# Compass.net
KiCad netlist of a schematic drawn in Altium Designer
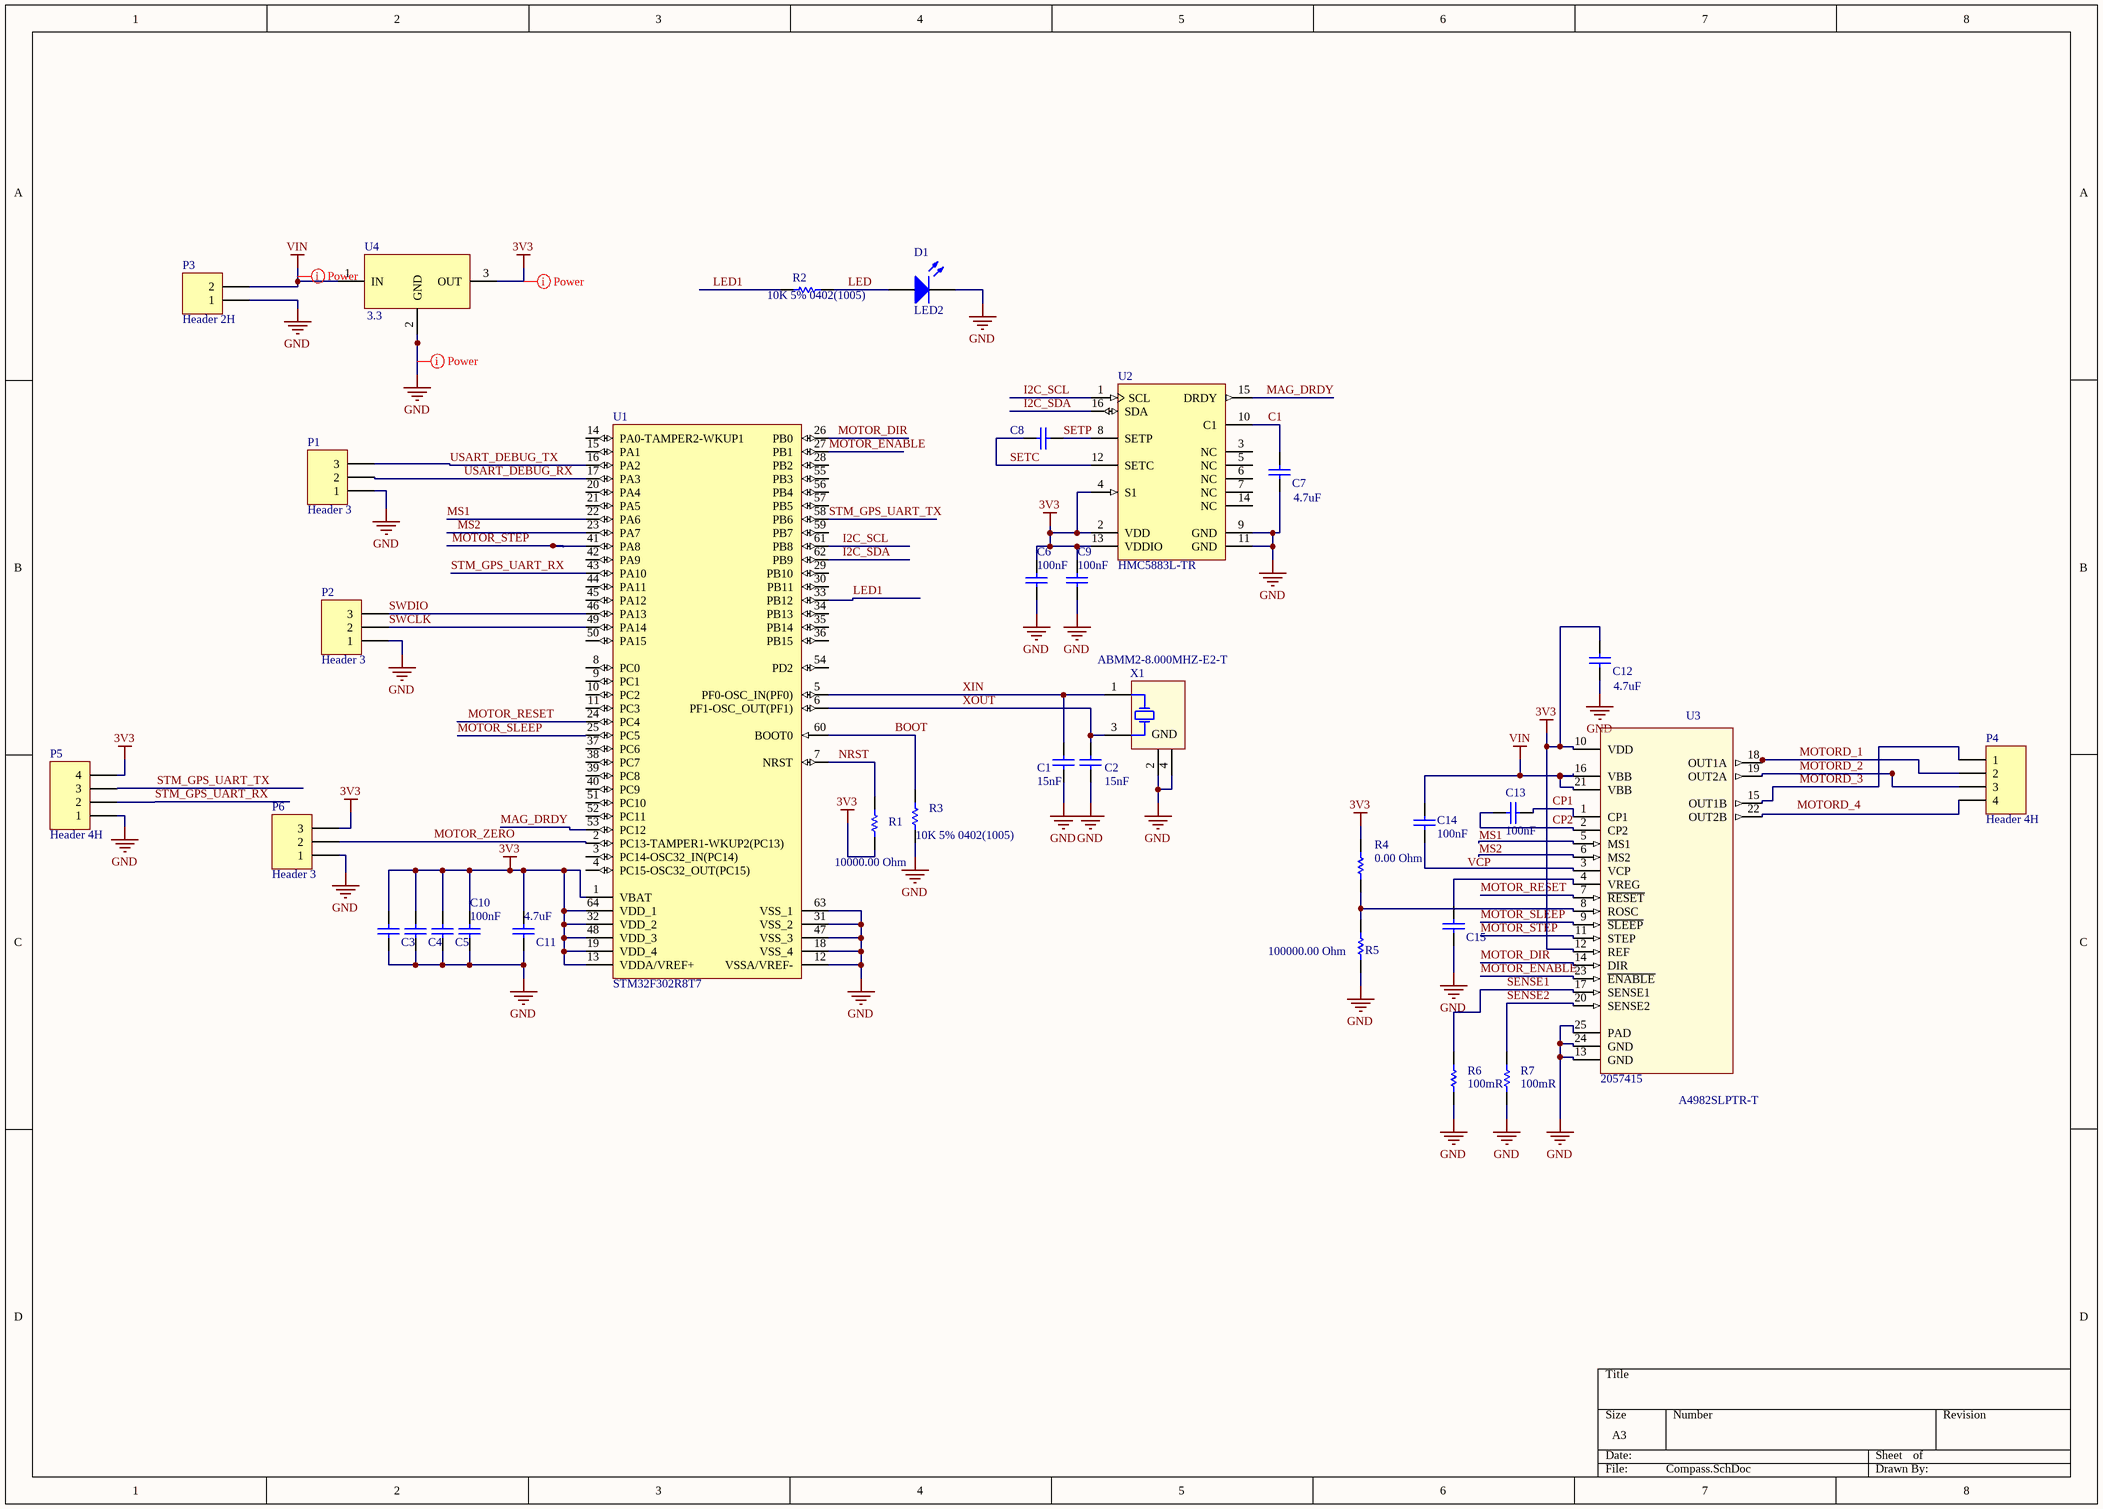
[diagram p0: Compass.SchDoc]

(export (version "E")
  (design (tool "Eeschema 10.0.6"))
  (components
    (comp (ref "C1")
      (value "15nF")
      (footprint "CAPC0402(1005)60_M")
      (description "CAP 15nF 6.3V ±20% 0402 (1005 Metric) Thickness 0.6mm SMD")
      (fields (field (name "TOLERANCE") "Â±20%") (field (name "Comment") "CAP 15nF 6.3V 0402(1005)"))
      (libsource (lib "Altium Content Vault") (part "CMP-1034-01907-1"))
    )
    (comp (ref "C2")
      (value "15nF")
      (footprint "CAPC0402(1005)60_M")
      (description "CAP 15nF 6.3V ±20% 0402 (1005 Metric) Thickness 0.6mm SMD")
      (fields (field (name "TOLERANCE") "Â±20%") (field (name "Comment") "CAP 15nF 6.3V 0402(1005)"))
      (libsource (lib "Altium Content Vault") (part "CMP-1034-01907-1"))
    )
    (comp (ref "C3")
      (value "CAP 100nF 6.3V 0603(1608)")
      (footprint "CAPC0603(1608)100_M")
      (description "CAP 100nF 6.3V ±10% 0603 (1608 Metric) Thickness 1mm SMD")
      (fields (field (name "TOLERANCE") "Â±10%"))
      (libsource (lib "Altium Content Vault") (part "CAP"))
    )
    (comp (ref "C4")
      (value "CAP 100nF 6.3V 0603(1608)")
      (footprint "CAPC0603(1608)100_M")
      (description "CAP 100nF 6.3V ±10% 0603 (1608 Metric) Thickness 1mm SMD")
      (fields (field (name "TOLERANCE") "Â±10%"))
      (libsource (lib "Altium Content Vault") (part "CAP"))
    )
    (comp (ref "C5")
      (value "CAP 100nF 6.3V 0603(1608)")
      (footprint "CAPC0603(1608)100_M")
      (description "CAP 100nF 6.3V ±10% 0603 (1608 Metric) Thickness 1mm SMD")
      (fields (field (name "TOLERANCE") "Â±10%"))
      (libsource (lib "Altium Content Vault") (part "CAP"))
    )
    (comp (ref "C6")
      (value "100nF")
      (footprint "CAPC0603(1608)100_M")
      (description "CAP 100nF 6.3V ±10% 0603 (1608 Metric) Thickness 1mm SMD")
      (fields (field (name "TOLERANCE") "Â±10%") (field (name "Comment") "CAP 100nF 6.3V 0603(1608)"))
      (libsource (lib "Altium Content Vault") (part "CMP-1035-02576-1"))
    )
    (comp (ref "C7")
      (value "4.7uF")
      (footprint "CAPC0603(1608)100_M")
      (description "CAP 4.7uF 6.3V ±20% 0603 (1608 Metric) Thickness 1mm SMD")
      (fields (field (name "TOLERANCE") "Â±20%") (field (name "Comment") "CAP 4.7uF 6.3V 0603(1608)"))
      (libsource (lib "Altium Content Vault") (part "CMP-1035-02782-1"))
    )
    (comp (ref "C8")
      (value "CAP 220nF 6.3V 0402(1005)")
      (footprint "CAPC0402(1005)60_L")
      (description "CAP 220nF 6.3V ±10% 0402 (1005 Metric) Thickness 0.6mm SMD")
      (fields (field (name "TOLERANCE") "Â±10%"))
      (libsource (lib "Altium Content Vault") (part "CAP"))
    )
    (comp (ref "C9")
      (value "100nF")
      (footprint "CAPC0603(1608)100_M")
      (description "CAP 100nF 6.3V ±10% 0603 (1608 Metric) Thickness 1mm SMD")
      (fields (field (name "TOLERANCE") "Â±10%") (field (name "Comment") "CAP 100nF 6.3V 0603(1608)"))
      (libsource (lib "Altium Content Vault") (part "CMP-1035-02576-1"))
    )
    (comp (ref "C10")
      (value "100nF")
      (footprint "CAPC0603(1608)100_M")
      (description "CAP 100nF 6.3V ±10% 0603 (1608 Metric) Thickness 1mm SMD")
      (fields (field (name "TOLERANCE") "Â±10%") (field (name "Comment") "CAP 100nF 6.3V 0603(1608)"))
      (libsource (lib "Altium Content Vault") (part "CMP-1035-02576-1"))
    )
    (comp (ref "C11")
      (value "4.7uF")
      (footprint "CAPC0603(1608)100_M")
      (description "CAP 4.7uF 6.3V ±20% 0603 (1608 Metric) Thickness 1mm SMD")
      (fields (field (name "TOLERANCE") "Â±20%") (field (name "Comment") "CAP 4.7uF 6.3V 0603(1608)"))
      (libsource (lib "Altium Content Vault") (part "CMP-1035-02782-1"))
    )
    (comp (ref "C12")
      (value "4.7uF")
      (footprint "CAPC0603(1608)100_M")
      (description "CAP 4.7uF 6.3V ±20% 0603 (1608 Metric) Thickness 1mm SMD")
      (fields (field (name "TOLERANCE") "Â±20%") (field (name "Comment") "CAP 4.7uF 6.3V 0603(1608)"))
      (libsource (lib "Altium Content Vault") (part "CMP-1035-02782-1"))
    )
    (comp (ref "C13")
      (value "100nF")
      (footprint "CAPC0603(1608)100_M")
      (description "CAP 100nF 6.3V ±10% 0603 (1608 Metric) Thickness 1mm SMD")
      (fields (field (name "TOLERANCE") "Â±10%") (field (name "Comment") "CAP 100nF 6.3V 0603(1608)"))
      (libsource (lib "Altium Content Vault") (part "CMP-1035-02576-1"))
    )
    (comp (ref "C14")
      (value "100nF")
      (footprint "CAPC0603(1608)100_M")
      (description "CAP 100nF 6.3V ±10% 0603 (1608 Metric) Thickness 1mm SMD")
      (fields (field (name "TOLERANCE") "Â±10%") (field (name "Comment") "CAP 100nF 6.3V 0603(1608)"))
      (libsource (lib "Altium Content Vault") (part "CMP-1035-02576-1"))
    )
    (comp (ref "C15")
      (value "CAP 220nF 6.3V 0402(1005)")
      (footprint "CAPC0402(1005)60_L")
      (description "CAP 220nF 6.3V ±10% 0402 (1005 Metric) Thickness 0.6mm SMD")
      (fields (field (name "TOLERANCE") "Â±10%"))
      (libsource (lib "Altium Content Vault") (part "CAP"))
    )
    (comp (ref "D1")
      (value "LED2")
      (footprint "3.2X1.6X1.1")
      (description "Typical RED, GREEN, YELLOW, AMBER GaAs LED")
      (fields (field (name "PUBLISHER") "Altium Limited"))
      (libsource (lib "Miscellaneous Devices") (part "LED2"))
    )
    (comp (ref "P1")
      (value "Header 3")
      (footprint "HDR1X3")
      (description "Header, 3-Pin")
      (fields (field (name "PUBLISHER") "Altium Limited"))
      (libsource (lib "Miscellaneous Connectors") (part "Header 3"))
    )
    (comp (ref "P2")
      (value "Header 3")
      (footprint "HDR1X3")
      (description "Header, 3-Pin")
      (fields (field (name "PUBLISHER") "Altium Limited"))
      (libsource (lib "Miscellaneous Connectors") (part "Header 3"))
    )
    (comp (ref "P3")
      (value "Header 2H")
      (footprint "HDR1X2H")
      (description "Header, 2-Pin, Right Angle")
      (fields (field (name "PUBLISHER") "Altium Limited"))
      (libsource (lib "Miscellaneous Connectors") (part "Header 2H"))
    )
    (comp (ref "P4")
      (value "Header 4H")
      (footprint "HDR1X4H")
      (description "Header, 4-Pin, Right Angle")
      (fields (field (name "PUBLISHER") "Altium Limited"))
      (libsource (lib "Miscellaneous Connectors") (part "Header 4H"))
    )
    (comp (ref "P5")
      (value "Header 4H")
      (footprint "HDR1X4H")
      (description "Header, 4-Pin, Right Angle")
      (fields (field (name "PUBLISHER") "Altium Limited"))
      (libsource (lib "") (part "Header 4H_1"))
    )
    (comp (ref "P6")
      (value "Header 3")
      (footprint "HDR1X3")
      (description "Header, 3-Pin")
      (fields (field (name "PUBLISHER") "Altium Limited"))
      (libsource (lib "Miscellaneous Connectors") (part "Header 3"))
    )
    (comp (ref "R1")
      (value "10000.00 Ohm")
      (footprint "RESC0402(1005)_N")
      (description "10K 0.063W 5% 0402 (1005 Metric)  SMD")
      (fields (field (name "TOLERANCE") "5 %") (field (name "POWER") "0.063 W"))
      (libsource (lib "Altium Content Vault") (part "CMP-1011-00098-1"))
    )
    (comp (ref "R2")
      (value "10K 5% 0402(1005)")
      (footprint "RESC0402(1005)_N")
      (description "10K 0.063W 5% 0402 (1005 Metric)  SMD")
      (fields (field (name "TOLERANCE") "5 %") (field (name "POWER") "0.063 W"))
      (libsource (lib "Altium Content Vault") (part "CMP-1011-00098-1"))
    )
    (comp (ref "R3")
      (value "10K 5% 0402(1005)")
      (footprint "RESC0402(1005)_N")
      (description "10K 0.063W 5% 0402 (1005 Metric)  SMD")
      (fields (field (name "TOLERANCE") "5 %") (field (name "POWER") "0.063 W"))
      (libsource (lib "Altium Content Vault") (part "CMP-1011-00098-1"))
    )
    (comp (ref "R4")
      (value "0.00 Ohm")
      (footprint "RESC0402(1005)_N")
      (description "Jumper 0402 (1005 Metric)")
      (fields (field (name "TOLERANCE") "None") (field (name "Comment") "Jumper 0402(1005)"))
      (libsource (lib "Altium Content Vault") (part "CMP-1011-00001-1"))
    )
    (comp (ref "R5")
      (value "100000.00 Ohm")
      (footprint "RESC0402(1005)_M")
      (description "100K 0.063W 1% 0402 (1005 Metric)  SMD")
      (fields (field (name "POWER") "0.063 W") (field (name "TOLERANCE") "1 %"))
      (libsource (lib "Altium Content Vault") (part "CMP-1011-00736-1"))
    )
    (comp (ref "R6")
      (value "100mR")
      (footprint "RESC0603(1608)_L")
      (description "0603 (1608 Metric) Chip Resistor")
      (fields (field (name "Comment") "RES0603"))
      (libsource (lib "Altium Content Vault") (part "CMP-1591-00001-1"))
    )
    (comp (ref "R7")
      (value "100mR")
      (footprint "RESC0603(1608)_L")
      (description "0603 (1608 Metric) Chip Resistor")
      (fields (field (name "Comment") "RES0603"))
      (libsource (lib "Altium Content Vault") (part "CMP-1591-00001-1"))
    )
    (comp (ref "U1")
      (value "STM32F302R8T7")
      (footprint "STM-LQFP64_N")
      (libsource (lib "Altium Content Vault") (part "MC-ARM-STM32F30X-LQFP64"))
    )
    (comp (ref "U2")
      (value "HMC5883L-TR")
      (footprint "HONEY-LPCC-16_V")
      (description "Three-Axis Digital Compass IC, 2.16 to 3.6 V, -30 to 85 degC, 16-Pin PLCC, RoHS, Tape and Reel")
      (fields (field (name "MANUFACTURER") "Honeywell"))
      (libsource (lib "Altium Content Vault") (part "HONEY-HMC5883L-TR-LPCC-16"))
    )
    (comp (ref "U3")
      (value "A4982SLPTR-T")
      (footprint "*SOP65P640X120-25N")
      (description "DMOS Microstepping Driver with Translator and Overcurrent Protection")
      (fields (field (name "MF") "Allegro") (field (name "SUPPLIER PART NUMBER 1") "2057415"))
      (libsource (lib "A4982SLPTR-T") (part "A4982SLPTR-T"))
    )
    (comp (ref "U4")
      (value "3.3")
      (footprint "TR05:SIP-3")
      (description "3V3 SMPS")
      (libsource (lib "TR05") (part "PSU"))
    )
    (comp (ref "X1")
      (value "ABMM2-8.000MHZ-E2-T")
      (footprint "ABRA-ABMM2-4_V")
      (fields (field (name "MANUFACTURER") "Abracon"))
      (libsource (lib "Altium Content Vault") (part "ABRA-XTAL_1-3-4"))
    )
  )
  (nets
    (net (code "1") (name "/BOOT") (class "Default")
      (node (ref "R3") (pin "2") (pinfunction "2_2") (pintype "passive"))
      (node (ref "U1") (pin "60") (pinfunction "BOOT0_60") (pintype "input"))
    )
    (net (code "2") (name "/C1") (class "Default")
      (node (ref "C7") (pin "2") (pinfunction "2_2") (pintype "passive"))
      (node (ref "U2") (pin "10") (pinfunction "C1_10") (pintype "passive"))
    )
    (net (code "3") (name "/CP1") (class "Default")
      (node (ref "C13") (pin "1") (pinfunction "1_1") (pintype "passive"))
      (node (ref "U3") (pin "1") (pinfunction "CP1_1") (pintype "passive"))
    )
    (net (code "4") (name "/CP2") (class "Default")
      (node (ref "C13") (pin "2") (pinfunction "2_2") (pintype "passive"))
      (node (ref "U3") (pin "2") (pinfunction "CP2_2") (pintype "passive"))
    )
    (net (code "5") (name "/I2C_SCL") (class "Default")
      (node (ref "U1") (pin "61") (pinfunction "PB8_61") (pintype "bidirectional"))
      (node (ref "U2") (pin "1") (pinfunction "SCL_1") (pintype "input"))
    )
    (net (code "6") (name "/I2C_SDA") (class "Default")
      (node (ref "U1") (pin "62") (pinfunction "PB9_62") (pintype "bidirectional"))
      (node (ref "U2") (pin "16") (pinfunction "SDA_16") (pintype "bidirectional"))
    )
    (net (code "7") (name "/LED") (class "Default")
      (node (ref "D1") (pin "1") (pinfunction "A_1") (pintype "passive"))
      (node (ref "R2") (pin "1") (pinfunction "1_1") (pintype "passive"))
    )
    (net (code "8") (name "/LED1") (class "Default")
      (node (ref "R2") (pin "2") (pinfunction "2_2") (pintype "passive"))
      (node (ref "U1") (pin "33") (pinfunction "PB12_33") (pintype "bidirectional"))
    )
    (net (code "9") (name "/MAG_DRDY") (class "Default")
      (node (ref "U1") (pin "53") (pinfunction "PC12_53") (pintype "bidirectional"))
      (node (ref "U2") (pin "15") (pinfunction "DRDY_15") (pintype "output"))
    )
    (net (code "10") (name "/MOTORD_1") (class "Default")
      (node (ref "P4") (pin "2") (pinfunction "2_2") (pintype "passive"))
      (node (ref "U3") (pin "18") (pinfunction "OUT1A_18") (pintype "output"))
    )
    (net (code "11") (name "/MOTORD_2") (class "Default")
      (node (ref "P4") (pin "3") (pinfunction "3_3") (pintype "passive"))
      (node (ref "U3") (pin "19") (pinfunction "OUT2A_19") (pintype "output"))
    )
    (net (code "12") (name "/MOTORD_3") (class "Default")
      (node (ref "P4") (pin "1") (pinfunction "1_1") (pintype "passive"))
      (node (ref "U3") (pin "15") (pinfunction "OUT1B_15") (pintype "output"))
    )
    (net (code "14") (name "/MOTOR_DIR") (class "Default")
      (node (ref "U1") (pin "26") (pinfunction "PB0_26") (pintype "bidirectional"))
      (node (ref "U3") (pin "14") (pinfunction "DIR_14") (pintype "input"))
    )
    (net (code "15") (name "/MOTOR_ENABLE") (class "Default")
      (node (ref "U1") (pin "27") (pinfunction "PB1_27") (pintype "bidirectional"))
      (node (ref "U3") (pin "23") (pinfunction "~{ENABLE}_23") (pintype "input"))
    )
    (net (code "16") (name "/MOTOR_RESET") (class "Default")
      (node (ref "U1") (pin "24") (pinfunction "PC4_24") (pintype "bidirectional"))
      (node (ref "U3") (pin "7") (pinfunction "~{RESET}_7") (pintype "input"))
    )
    (net (code "17") (name "/MOTOR_SLEEP") (class "Default")
      (node (ref "U1") (pin "25") (pinfunction "PC5_25") (pintype "bidirectional"))
      (node (ref "U3") (pin "9") (pinfunction "~{SLEEP}_9") (pintype "input"))
    )
    (net (code "18") (name "/MOTOR_STEP") (class "Default")
      (node (ref "U1") (pin "41") (pinfunction "PA8_41") (pintype "bidirectional"))
      (node (ref "U3") (pin "11") (pinfunction "STEP_11") (pintype "input"))
    )
    (net (code "19") (name "/MOTOR_ZERO") (class "Default")
      (node (ref "P6") (pin "2") (pinfunction "2_2") (pintype "passive"))
      (node (ref "U1") (pin "2") (pinfunction "PC13-TAMPER1-WKUP2(PC13)_2") (pintype "bidirectional"))
    )
    (net (code "20") (name "/MS1") (class "Default")
      (node (ref "U1") (pin "22") (pinfunction "PA6_22") (pintype "bidirectional"))
      (node (ref "U3") (pin "5") (pinfunction "MS1_5") (pintype "input"))
    )
    (net (code "21") (name "/MS2") (class "Default")
      (node (ref "U1") (pin "23") (pinfunction "PA7_23") (pintype "bidirectional"))
      (node (ref "U3") (pin "6") (pinfunction "MS2_6") (pintype "input"))
    )
    (net (code "22") (name "/NRST") (class "Default")
      (node (ref "R1") (pin "2") (pinfunction "2_2") (pintype "passive"))
      (node (ref "U1") (pin "7") (pinfunction "NRST_7") (pintype "bidirectional"))
    )
    (net (code "23") (name "/SENSE1") (class "Default")
      (node (ref "R6") (pin "2") (pinfunction "2_2") (pintype "passive"))
      (node (ref "U3") (pin "17") (pinfunction "SENSE1_17") (pintype "input"))
    )
    (net (code "24") (name "/SENSE2") (class "Default")
      (node (ref "R7") (pin "2") (pinfunction "2_2") (pintype "passive"))
      (node (ref "U3") (pin "20") (pinfunction "SENSE2_20") (pintype "input"))
    )
    (net (code "25") (name "/SETC") (class "Default")
      (node (ref "C8") (pin "1") (pinfunction "1_1") (pintype "passive"))
      (node (ref "U2") (pin "12") (pinfunction "SETC_12") (pintype "passive"))
    )
    (net (code "27") (name "/SETP") (class "Default")
      (node (ref "C8") (pin "2") (pinfunction "2_2") (pintype "passive"))
      (node (ref "U2") (pin "8") (pinfunction "SETP_8") (pintype "passive"))
    )
    (net (code "28") (name "/STM_GPS_UART_RX") (class "Default")
      (node (ref "P5") (pin "2") (pinfunction "2_2") (pintype "passive"))
      (node (ref "U1") (pin "43") (pinfunction "PA10_43") (pintype "bidirectional"))
    )
    (net (code "29") (name "/STM_GPS_UART_TX") (class "Default")
      (node (ref "P5") (pin "3") (pinfunction "3_3") (pintype "passive"))
      (node (ref "U1") (pin "58") (pinfunction "PB6_58") (pintype "bidirectional"))
    )
    (net (code "30") (name "/SWCLK") (class "Default")
      (node (ref "P2") (pin "2") (pinfunction "2_2") (pintype "passive"))
      (node (ref "U1") (pin "49") (pinfunction "PA14_49") (pintype "bidirectional"))
    )
    (net (code "31") (name "/SWDIO") (class "Default")
      (node (ref "P2") (pin "3") (pinfunction "3_3") (pintype "passive"))
      (node (ref "U1") (pin "46") (pinfunction "PA13_46") (pintype "bidirectional"))
    )
    (net (code "32") (name "/USART_DEBUG_RX") (class "Default")
      (node (ref "P1") (pin "2") (pinfunction "2_2") (pintype "passive"))
      (node (ref "U1") (pin "17") (pinfunction "PA3_17") (pintype "bidirectional"))
    )
    (net (code "34") (name "/USART_DEBUG_TX") (class "Default")
      (node (ref "P1") (pin "3") (pinfunction "3_3") (pintype "passive"))
      (node (ref "U1") (pin "16") (pinfunction "PA2_16") (pintype "bidirectional"))
    )
    (net (code "35") (name "/XIN") (class "Default")
      (node (ref "C1") (pin "2") (pinfunction "2_2") (pintype "passive"))
      (node (ref "U1") (pin "5") (pinfunction "PF0-OSC_IN(PF0)_5") (pintype "bidirectional"))
      (node (ref "X1") (pin "1") (pinfunction "X1_1") (pintype "passive"))
    )
    (net (code "36") (name "/XOUT") (class "Default")
      (node (ref "C2") (pin "2") (pinfunction "2_2") (pintype "passive"))
      (node (ref "U1") (pin "6") (pinfunction "PF1-OSC_OUT(PF1)_6") (pintype "bidirectional"))
      (node (ref "X1") (pin "3") (pinfunction "X2_3") (pintype "passive"))
    )
    (net (code "37") (name "3V3") (class "Default")
      (node (ref "C10") (pin "2") (pinfunction "2_2") (pintype "passive"))
      (node (ref "C11") (pin "2") (pinfunction "2_2") (pintype "passive"))
      (node (ref "C12") (pin "2") (pinfunction "2_2") (pintype "passive"))
      (node (ref "C3") (pin "2") (pinfunction "2_2") (pintype "passive"))
      (node (ref "C4") (pin "2") (pinfunction "2_2") (pintype "passive"))
      (node (ref "C5") (pin "2") (pinfunction "2_2") (pintype "passive"))
      (node (ref "C6") (pin "2") (pinfunction "2_2") (pintype "passive"))
      (node (ref "C9") (pin "2") (pinfunction "2_2") (pintype "passive"))
      (node (ref "P5") (pin "4") (pinfunction "4_4") (pintype "passive"))
      (node (ref "P6") (pin "3") (pinfunction "3_3") (pintype "passive"))
      (node (ref "R1") (pin "1") (pinfunction "1_1") (pintype "passive"))
      (node (ref "R4") (pin "2") (pinfunction "2_2") (pintype "passive"))
      (node (ref "U1") (pin "1") (pinfunction "VBAT_1") (pintype "power_in"))
      (node (ref "U1") (pin "13") (pinfunction "VDDA/VREF+_13") (pintype "power_in"))
      (node (ref "U1") (pin "19") (pinfunction "VDD_4_19") (pintype "power_in"))
      (node (ref "U1") (pin "32") (pinfunction "VDD_2_32") (pintype "power_in"))
      (node (ref "U1") (pin "48") (pinfunction "VDD_3_48") (pintype "power_in"))
      (node (ref "U1") (pin "64") (pinfunction "VDD_1_64") (pintype "power_in"))
      (node (ref "U2") (pin "13") (pinfunction "VDDIO_13") (pintype "power_in"))
      (node (ref "U2") (pin "2") (pinfunction "VDD_2") (pintype "power_in"))
      (node (ref "U2") (pin "4") (pinfunction "S1_4") (pintype "input"))
      (node (ref "U3") (pin "10") (pinfunction "VDD_10") (pintype "power_in"))
      (node (ref "U3") (pin "12") (pinfunction "REF_12") (pintype "input"))
      (node (ref "U4") (pin "3") (pinfunction "OUT_3") (pintype "power_in"))
    )
    (net (code "38") (name "GND") (class "Default")
      (node (ref "C1") (pin "1") (pinfunction "1_1") (pintype "passive"))
      (node (ref "C10") (pin "1") (pinfunction "1_1") (pintype "passive"))
      (node (ref "C11") (pin "1") (pinfunction "1_1") (pintype "passive"))
      (node (ref "C12") (pin "1") (pinfunction "1_1") (pintype "passive"))
      (node (ref "C15") (pin "1") (pinfunction "1_1") (pintype "passive"))
      (node (ref "C2") (pin "1") (pinfunction "1_1") (pintype "passive"))
      (node (ref "C3") (pin "1") (pinfunction "1_1") (pintype "passive"))
      (node (ref "C4") (pin "1") (pinfunction "1_1") (pintype "passive"))
      (node (ref "C5") (pin "1") (pinfunction "1_1") (pintype "passive"))
      (node (ref "C6") (pin "1") (pinfunction "1_1") (pintype "passive"))
      (node (ref "C7") (pin "1") (pinfunction "1_1") (pintype "passive"))
      (node (ref "C9") (pin "1") (pinfunction "1_1") (pintype "passive"))
      (node (ref "D1") (pin "2") (pinfunction "K_2") (pintype "passive"))
      (node (ref "P1") (pin "1") (pinfunction "1_1") (pintype "passive"))
      (node (ref "P2") (pin "1") (pinfunction "1_1") (pintype "passive"))
      (node (ref "P3") (pin "1") (pinfunction "1_1") (pintype "passive"))
      (node (ref "P5") (pin "1") (pinfunction "1_1") (pintype "passive"))
      (node (ref "P6") (pin "1") (pinfunction "1_1") (pintype "passive"))
      (node (ref "R3") (pin "1") (pinfunction "1_1") (pintype "passive"))
      (node (ref "R5") (pin "1") (pinfunction "1_1") (pintype "passive"))
      (node (ref "R6") (pin "1") (pinfunction "1_1") (pintype "passive"))
      (node (ref "R7") (pin "1") (pinfunction "1_1") (pintype "passive"))
      (node (ref "U1") (pin "12") (pinfunction "VSSA/VREF-_12") (pintype "power_in"))
      (node (ref "U1") (pin "18") (pinfunction "VSS_4_18") (pintype "power_in"))
      (node (ref "U1") (pin "31") (pinfunction "VSS_2_31") (pintype "power_in"))
      (node (ref "U1") (pin "47") (pinfunction "VSS_3_47") (pintype "power_in"))
      (node (ref "U1") (pin "63") (pinfunction "VSS_1_63") (pintype "power_in"))
      (node (ref "U2") (pin "11") (pinfunction "GND_11") (pintype "power_in"))
      (node (ref "U2") (pin "9") (pinfunction "GND_9") (pintype "power_in"))
      (node (ref "U3") (pin "13") (pinfunction "GND_13") (pintype "passive"))
      (node (ref "U3") (pin "24") (pinfunction "GND_24") (pintype "power_in"))
      (node (ref "U3") (pin "25") (pinfunction "PAD_25") (pintype "power_in"))
      (node (ref "U4") (pin "2") (pinfunction "GND_2") (pintype "power_in"))
      (node (ref "X1") (pin "2") (pinfunction "GND_2") (pintype "power_in"))
      (node (ref "X1") (pin "4") (pinfunction "GND_4") (pintype "power_in"))
    )
    (net (code "39") (name "Net-(U3-OUT2B)") (class "Default")
      (node (ref "P4") (pin "4") (pinfunction "4_4") (pintype "passive"))
      (node (ref "U3") (pin "22") (pinfunction "OUT2B_22") (pintype "output"))
    )
    (net (code "40") (name "Net-(U3-ROSC)") (class "Default")
      (node (ref "R4") (pin "1") (pinfunction "1_1") (pintype "passive"))
      (node (ref "R5") (pin "2") (pinfunction "2_2") (pintype "passive"))
      (node (ref "U3") (pin "8") (pinfunction "ROSC_8") (pintype "input"))
    )
    (net (code "41") (name "Net-(U3-VCP)") (class "Default")
      (node (ref "C14") (pin "1") (pinfunction "1_1") (pintype "passive"))
      (node (ref "U3") (pin "3") (pinfunction "VCP_3") (pintype "passive"))
    )
    (net (code "42") (name "Net-(U3-VREG)") (class "Default")
      (node (ref "C15") (pin "2") (pinfunction "2_2") (pintype "passive"))
      (node (ref "U3") (pin "4") (pinfunction "VREG_4") (pintype "passive"))
    )
    (net (code "43") (name "VIN") (class "Default")
      (node (ref "C14") (pin "2") (pinfunction "2_2") (pintype "passive"))
      (node (ref "P3") (pin "2") (pinfunction "2_2") (pintype "passive"))
      (node (ref "U3") (pin "16") (pinfunction "VBB_16") (pintype "power_in"))
      (node (ref "U3") (pin "21") (pinfunction "VBB_21") (pintype "power_in"))
      (node (ref "U4") (pin "1") (pinfunction "IN_1") (pintype "power_in"))
    )
    (net (code "44") (name "unconnected-(U1-PA0-TAMPER2-WKUP1-Pad14)") (class "Default")
      (node (ref "U1") (pin "14") (pinfunction "PA0-TAMPER2-WKUP1_14") (pintype "bidirectional"))
    )
    (net (code "45") (name "unconnected-(U1-PA1-Pad15)") (class "Default")
      (node (ref "U1") (pin "15") (pinfunction "PA1_15") (pintype "bidirectional"))
    )
    (net (code "46") (name "unconnected-(U1-PA4-Pad20)") (class "Default")
      (node (ref "U1") (pin "20") (pinfunction "PA4_20") (pintype "bidirectional"))
    )
    (net (code "47") (name "unconnected-(U1-PA5-Pad21)") (class "Default")
      (node (ref "U1") (pin "21") (pinfunction "PA5_21") (pintype "bidirectional"))
    )
    (net (code "48") (name "unconnected-(U1-PA9-Pad42)") (class "Default")
      (node (ref "U1") (pin "42") (pinfunction "PA9_42") (pintype "bidirectional"))
    )
    (net (code "49") (name "unconnected-(U1-PA11-Pad44)") (class "Default")
      (node (ref "U1") (pin "44") (pinfunction "PA11_44") (pintype "bidirectional"))
    )
    (net (code "50") (name "unconnected-(U1-PA12-Pad45)") (class "Default")
      (node (ref "U1") (pin "45") (pinfunction "PA12_45") (pintype "bidirectional"))
    )
    (net (code "51") (name "unconnected-(U1-PA15-Pad50)") (class "Default")
      (node (ref "U1") (pin "50") (pinfunction "PA15_50") (pintype "bidirectional"))
    )
    (net (code "52") (name "unconnected-(U1-PB2-Pad28)") (class "Default")
      (node (ref "U1") (pin "28") (pinfunction "PB2_28") (pintype "bidirectional"))
    )
    (net (code "53") (name "unconnected-(U1-PB3-Pad55)") (class "Default")
      (node (ref "U1") (pin "55") (pinfunction "PB3_55") (pintype "bidirectional"))
    )
    (net (code "54") (name "unconnected-(U1-PB4-Pad56)") (class "Default")
      (node (ref "U1") (pin "56") (pinfunction "PB4_56") (pintype "bidirectional"))
    )
    (net (code "55") (name "unconnected-(U1-PB5-Pad57)") (class "Default")
      (node (ref "U1") (pin "57") (pinfunction "PB5_57") (pintype "bidirectional"))
    )
    (net (code "56") (name "unconnected-(U1-PB7-Pad59)") (class "Default")
      (node (ref "U1") (pin "59") (pinfunction "PB7_59") (pintype "bidirectional"))
    )
    (net (code "57") (name "unconnected-(U1-PB10-Pad29)") (class "Default")
      (node (ref "U1") (pin "29") (pinfunction "PB10_29") (pintype "bidirectional"))
    )
    (net (code "58") (name "unconnected-(U1-PB11-Pad30)") (class "Default")
      (node (ref "U1") (pin "30") (pinfunction "PB11_30") (pintype "bidirectional"))
    )
    (net (code "59") (name "unconnected-(U1-PB13-Pad34)") (class "Default")
      (node (ref "U1") (pin "34") (pinfunction "PB13_34") (pintype "bidirectional"))
    )
    (net (code "60") (name "unconnected-(U1-PB14-Pad35)") (class "Default")
      (node (ref "U1") (pin "35") (pinfunction "PB14_35") (pintype "bidirectional"))
    )
    (net (code "61") (name "unconnected-(U1-PB15-Pad36)") (class "Default")
      (node (ref "U1") (pin "36") (pinfunction "PB15_36") (pintype "bidirectional"))
    )
    (net (code "62") (name "unconnected-(U1-PC0-Pad8)") (class "Default")
      (node (ref "U1") (pin "8") (pinfunction "PC0_8") (pintype "bidirectional"))
    )
    (net (code "63") (name "unconnected-(U1-PC1-Pad9)") (class "Default")
      (node (ref "U1") (pin "9") (pinfunction "PC1_9") (pintype "bidirectional"))
    )
    (net (code "64") (name "unconnected-(U1-PC2-Pad10)") (class "Default")
      (node (ref "U1") (pin "10") (pinfunction "PC2_10") (pintype "bidirectional"))
    )
    (net (code "65") (name "unconnected-(U1-PC3-Pad11)") (class "Default")
      (node (ref "U1") (pin "11") (pinfunction "PC3_11") (pintype "bidirectional"))
    )
    (net (code "66") (name "unconnected-(U1-PC6-Pad37)") (class "Default")
      (node (ref "U1") (pin "37") (pinfunction "PC6_37") (pintype "bidirectional"))
    )
    (net (code "67") (name "unconnected-(U1-PC7-Pad38)") (class "Default")
      (node (ref "U1") (pin "38") (pinfunction "PC7_38") (pintype "bidirectional"))
    )
    (net (code "68") (name "unconnected-(U1-PC8-Pad39)") (class "Default")
      (node (ref "U1") (pin "39") (pinfunction "PC8_39") (pintype "bidirectional"))
    )
    (net (code "69") (name "unconnected-(U1-PC9-Pad40)") (class "Default")
      (node (ref "U1") (pin "40") (pinfunction "PC9_40") (pintype "bidirectional"))
    )
    (net (code "70") (name "unconnected-(U1-PC10-Pad51)") (class "Default")
      (node (ref "U1") (pin "51") (pinfunction "PC10_51") (pintype "bidirectional"))
    )
    (net (code "71") (name "unconnected-(U1-PC11-Pad52)") (class "Default")
      (node (ref "U1") (pin "52") (pinfunction "PC11_52") (pintype "bidirectional"))
    )
    (net (code "72") (name "unconnected-(U1-PC14-OSC32_IN(PC14)-Pad3)") (class "Default")
      (node (ref "U1") (pin "3") (pinfunction "PC14-OSC32_IN(PC14)_3") (pintype "bidirectional"))
    )
    (net (code "73") (name "unconnected-(U1-PC15-OSC32_OUT(PC15)-Pad4)") (class "Default")
      (node (ref "U1") (pin "4") (pinfunction "PC15-OSC32_OUT(PC15)_4") (pintype "bidirectional"))
    )
    (net (code "74") (name "unconnected-(U1-PD2-Pad54)") (class "Default")
      (node (ref "U1") (pin "54") (pinfunction "PD2_54") (pintype "bidirectional"))
    )
    (net (code "75") (name "unconnected-(U2-NC-Pad3)") (class "Default")
      (node (ref "U2") (pin "3") (pinfunction "NC_3") (pintype "passive"))
    )
    (net (code "76") (name "unconnected-(U2-NC-Pad5)") (class "Default")
      (node (ref "U2") (pin "5") (pinfunction "NC_5") (pintype "passive"))
    )
    (net (code "77") (name "unconnected-(U2-NC-Pad6)") (class "Default")
      (node (ref "U2") (pin "6") (pinfunction "NC_6") (pintype "passive"))
    )
    (net (code "78") (name "unconnected-(U2-NC-Pad7)") (class "Default")
      (node (ref "U2") (pin "7") (pinfunction "NC_7") (pintype "passive"))
    )
    (net (code "79") (name "unconnected-(U2-NC-Pad14)") (class "Default")
      (node (ref "U2") (pin "14") (pinfunction "NC_14") (pintype "passive"))
    )
  )
)
